# LPS_3_3v_1A_12V_AZ1117H-3_3TRE1.net
KiCad netlist of a schematic drawn in Altium Designer
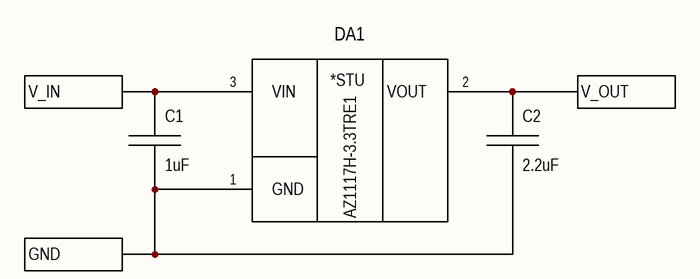
[diagram p0: LPS 3.3v 1A (12V) AZ1117H-3.3TRE1.SchDoc]

(export (version "E")
  (design (tool "Eeschema 10.0.6"))
  (components
    (comp (ref "C1")
      (value "1uF")
      (footprint "CAPC1608L")
      (description "Capacitor Ceramic 1uF 25V 0603(1608)")
      (fields (field (name "TOLERANCE") "±10%") (field (name "VOLTAGE") "25V"))
      (libsource (lib "Capacitors") (part "Capacitor Ceramic 1uF 25V 0603(1608)"))
    )
    (comp (ref "C2")
      (value "2.2uF")
      (footprint "CAPC2012L")
      (description "Capacitor Ceramic 2.2uF 50V 0805(2012)")
      (fields (field (name "TOLERANCE") "±10%") (field (name "VOLTAGE") "50V"))
      (libsource (lib "Capacitors") (part "Capacitor Ceramic 2.2uF 50V 0805(2012)"))
    )
    (comp (ref "DA1")
      (value "AZ1117H-3.3TRE1")
      (footprint "SOT-223")
      (description "LDO 1A 3.3V (15V)")
      (fields (field (name "MANUFACTURER") "Diodes Incorporated"))
      (libsource (lib "Power") (part "AZ1117H-3.3TRE1"))
    )
  )
  (nets
    (net (code "1") (name "/GND") (class "Default")
      (node (ref "C1") (pin "2") (pinfunction "2_2") (pintype "passive"))
      (node (ref "C2") (pin "2") (pinfunction "2_2") (pintype "passive"))
      (node (ref "DA1") (pin "1") (pinfunction "GND_1") (pintype "passive"))
    )
    (net (code "2") (name "/V_IN") (class "Default")
      (node (ref "C1") (pin "1") (pinfunction "1_1") (pintype "passive"))
      (node (ref "DA1") (pin "3") (pinfunction "VIN_3") (pintype "passive"))
    )
    (net (code "3") (name "/V_OUT") (class "Default")
      (node (ref "C2") (pin "1") (pinfunction "1_1") (pintype "passive"))
      (node (ref "DA1") (pin "2") (pinfunction "VOUT_2") (pintype "passive"))
    )
  )
)
